# lednode2.net
KiCad netlist of a schematic drawn in EAGLE
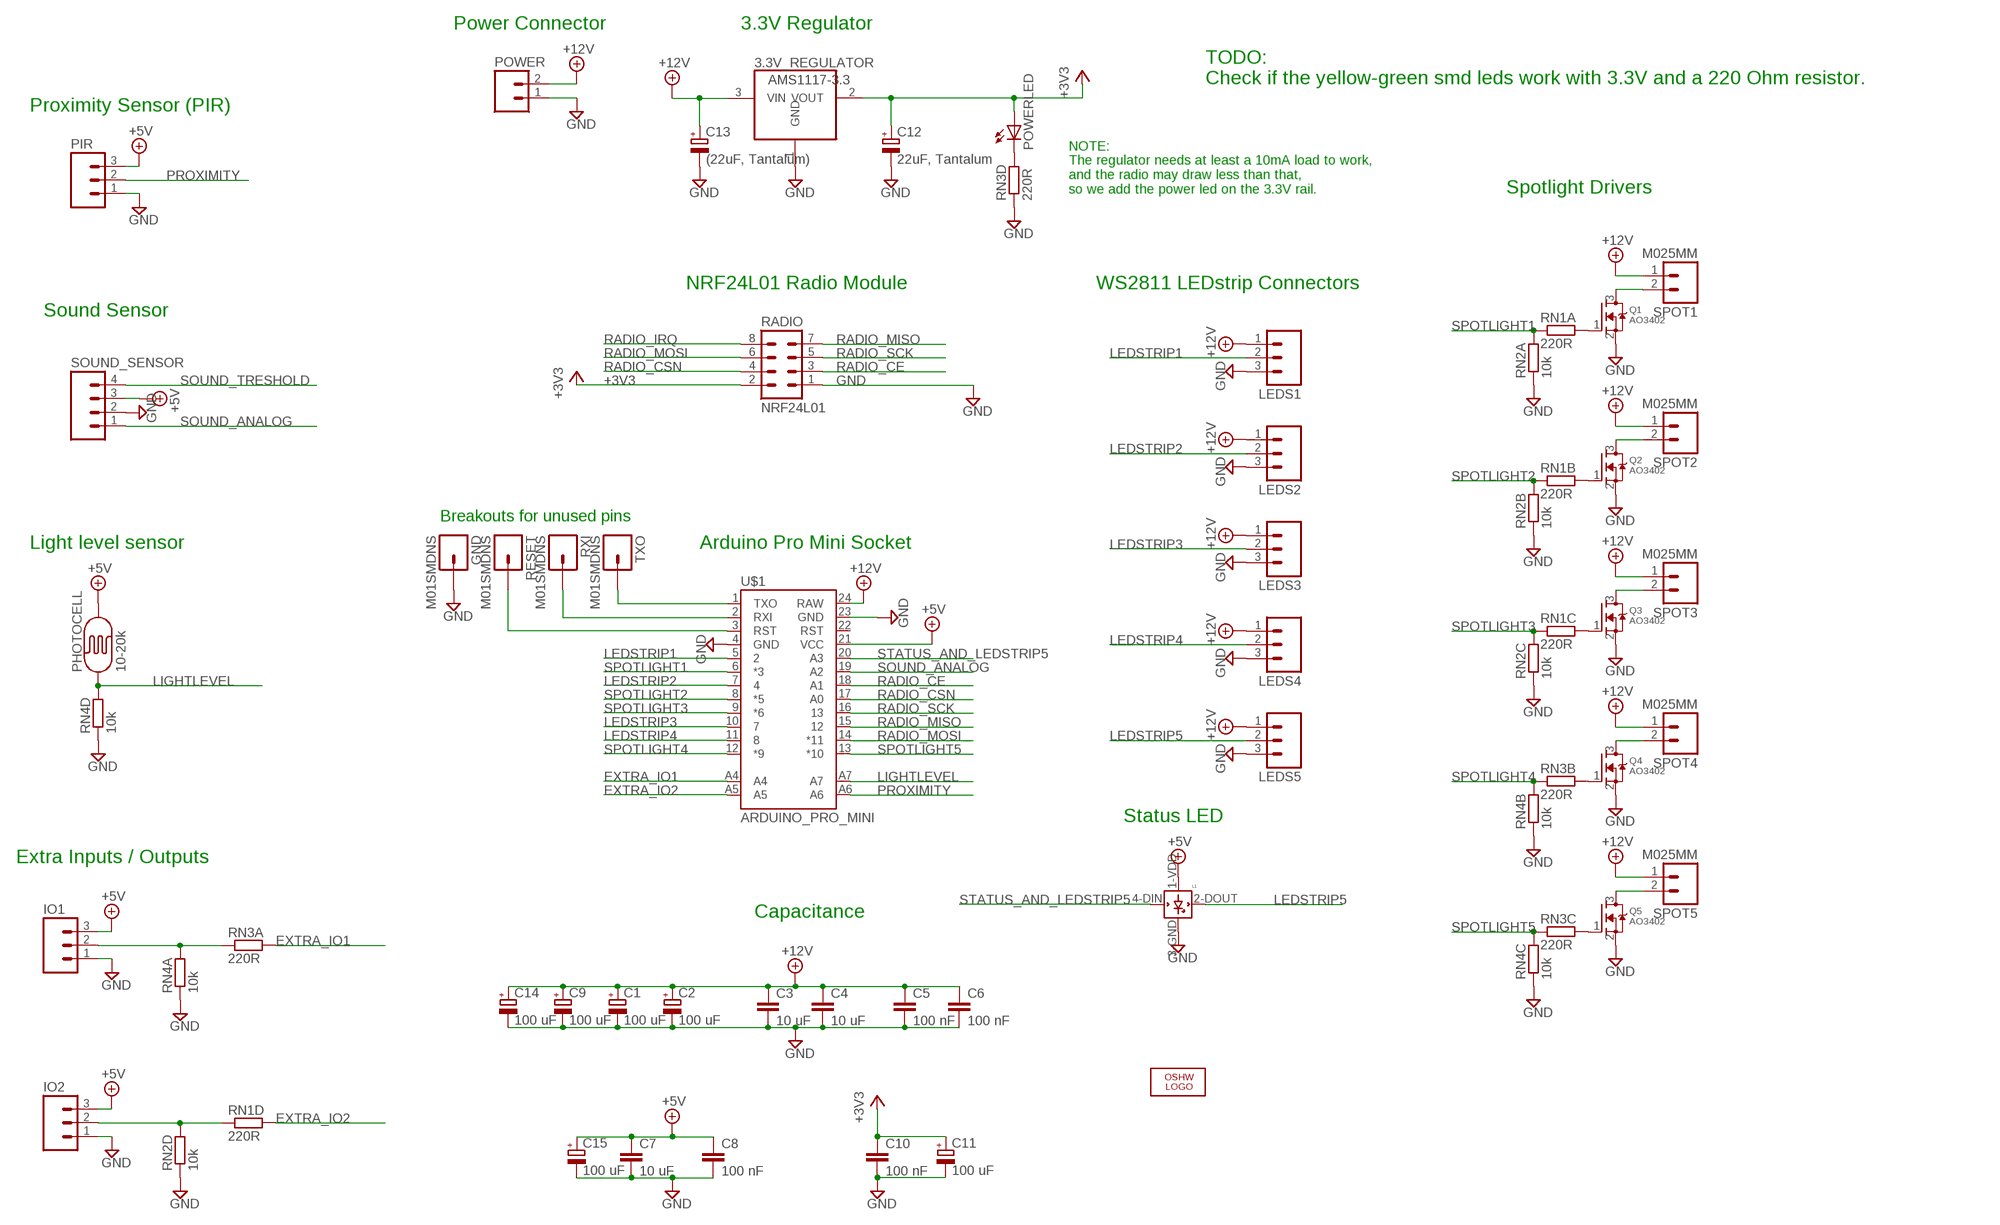
[diagram p0: schematic, sheet 1]

(export (version "E")
  (design (tool "Eeschema 10.0.6"))
  (components
    (comp (ref "3.3V_REGULATOR")
      (value "AMS1117-3.3")
      (footprint "eagle-import:SOT223")
      (fields (field (name "MPN") "REG1117"))
      (libsource (lib "eagle-import") (part "REG1117"))
    )
    (comp (ref "C1")
      (value "100 uF")
      (footprint "eagle-import:E2,5-6")
      (libsource (lib "eagle-import") (part "CPOL-EUE2.5-6"))
    )
    (comp (ref "C2")
      (value "100 uF")
      (footprint "eagle-import:E2,5-6")
      (libsource (lib "eagle-import") (part "CPOL-EUE2.5-6"))
    )
    (comp (ref "C3")
      (value "10 uF")
      (footprint "eagle-import:C1206")
      (libsource (lib "eagle-import") (part "C-EUC1206"))
    )
    (comp (ref "C4")
      (value "10 uF")
      (footprint "eagle-import:C1206")
      (libsource (lib "eagle-import") (part "C-EUC1206"))
    )
    (comp (ref "C5")
      (value "100 nF")
      (footprint "eagle-import:C0805")
      (libsource (lib "eagle-import") (part "C-EUC0805"))
    )
    (comp (ref "C6")
      (value "100 nF")
      (footprint "eagle-import:C0805")
      (libsource (lib "eagle-import") (part "C-EUC0805"))
    )
    (comp (ref "C7")
      (value "10 uF")
      (footprint "eagle-import:C1206")
      (libsource (lib "eagle-import") (part "C-EUC1206"))
    )
    (comp (ref "C8")
      (value "100 nF")
      (footprint "eagle-import:C0805")
      (libsource (lib "eagle-import") (part "C-EUC0805"))
    )
    (comp (ref "C9")
      (value "100 uF")
      (footprint "eagle-import:E2,5-6")
      (libsource (lib "eagle-import") (part "CPOL-EUE2.5-6"))
    )
    (comp (ref "C10")
      (value "100 nF")
      (footprint "eagle-import:C0805")
      (libsource (lib "eagle-import") (part "C-EUC0805"))
    )
    (comp (ref "C11")
      (value "100 uF")
      (footprint "eagle-import:E2,5-6")
      (libsource (lib "eagle-import") (part "CPOL-EUE2.5-6"))
    )
    (comp (ref "C12")
      (value "22uF, Tantalum")
      (footprint "eagle-import:SMC_A")
      (libsource (lib "eagle-import") (part "CPOL-EUSMCA"))
    )
    (comp (ref "C13")
      (value "(22uF, Tantalum)")
      (footprint "eagle-import:SMC_A")
      (libsource (lib "eagle-import") (part "CPOL-EUSMCA"))
    )
    (comp (ref "C14")
      (value "100 uF")
      (footprint "eagle-import:E2,5-6")
      (libsource (lib "eagle-import") (part "CPOL-EUE2.5-6"))
    )
    (comp (ref "C15")
      (value "100 uF")
      (footprint "eagle-import:E2,5-6")
      (libsource (lib "eagle-import") (part "CPOL-EUE2.5-6"))
    )
    (comp (ref "GND")
      (value "M01SMDNS")
      (footprint "eagle-import:1X01NS")
      (libsource (lib "eagle-import") (part "M01SMDNS"))
    )
    (comp (ref "IO1")
      (value "M03PTH")
      (footprint "eagle-import:1X03")
      (libsource (lib "eagle-import") (part "M03PTH"))
    )
    (comp (ref "IO2")
      (value "M03PTH")
      (footprint "eagle-import:1X03")
      (libsource (lib "eagle-import") (part "M03PTH"))
    )
    (comp (ref "L1")
      (value "WS2812B")
      (footprint "eagle-import:WS2812B")
      (libsource (lib "eagle-import") (part "WS2812B"))
    )
    (comp (ref "LEDS1")
      (value "M03LONGPADS")
      (footprint "eagle-import:1X03_LONGPADS")
      (libsource (lib "eagle-import") (part "M03LONGPADS"))
    )
    (comp (ref "LEDS2")
      (value "M03LONGPADS")
      (footprint "eagle-import:1X03_LONGPADS")
      (libsource (lib "eagle-import") (part "M03LONGPADS"))
    )
    (comp (ref "LEDS3")
      (value "M03LONGPADS")
      (footprint "eagle-import:1X03_LONGPADS")
      (libsource (lib "eagle-import") (part "M03LONGPADS"))
    )
    (comp (ref "LEDS4")
      (value "M03LONGPADS")
      (footprint "eagle-import:1X03_LONGPADS")
      (libsource (lib "eagle-import") (part "M03LONGPADS"))
    )
    (comp (ref "LEDS5")
      (value "M03LONGPADS")
      (footprint "eagle-import:1X03_LONGPADS")
      (libsource (lib "eagle-import") (part "M03LONGPADS"))
    )
    (comp (ref "LOGO3")
      (value "LOGO-OSHW-8MILX0100-NT")
      (footprint "eagle-import:OSHW_8X100_NOTEXT")
      (libsource (lib "eagle-import") (part "LOGO-OSHW-8MILX0100-NT"))
    )
    (comp (ref "PHOTOCELL")
      (value "10-20k")
      (footprint "eagle-import:PHOTOCELL")
      (libsource (lib "eagle-import") (part "PHOTOCELLPTH"))
    )
    (comp (ref "PIR")
      (value "M03PTH")
      (footprint "eagle-import:1X03")
      (libsource (lib "eagle-import") (part "M03PTH"))
    )
    (comp (ref "POWER")
      (value "M025MM")
      (footprint "eagle-import:SCREWTERMINAL-5MM-2")
      (libsource (lib "eagle-import") (part "M025MM"))
    )
    (comp (ref "POWERLED")
      (value "LEDSMT1206")
      (footprint "eagle-import:1206")
      (libsource (lib "eagle-import") (part "LEDSMT1206"))
    )
    (comp (ref "Q1")
      (value "AO3402")
      (footprint "eagle-import:SOT23-W")
      (libsource (lib "eagle-import") (part "MOSFET-NWAVE"))
    )
    (comp (ref "Q2")
      (value "AO3402")
      (footprint "eagle-import:SOT23-W")
      (libsource (lib "eagle-import") (part "MOSFET-NWAVE"))
    )
    (comp (ref "Q3")
      (value "AO3402")
      (footprint "eagle-import:SOT23-W")
      (libsource (lib "eagle-import") (part "MOSFET-NWAVE"))
    )
    (comp (ref "Q4")
      (value "AO3402")
      (footprint "eagle-import:SOT23-W")
      (libsource (lib "eagle-import") (part "MOSFET-NWAVE"))
    )
    (comp (ref "Q5")
      (value "AO3402")
      (footprint "eagle-import:SOT23-W")
      (libsource (lib "eagle-import") (part "MOSFET-NWAVE"))
    )
    (comp (ref "RADIO")
      (value "NRF24L01")
      (footprint "eagle-import:MA04-2")
      (libsource (lib "eagle-import") (part "MA04-2"))
    )
    (comp (ref "RESET")
      (value "M01SMDNS")
      (footprint "eagle-import:1X01NS")
      (libsource (lib "eagle-import") (part "M01SMDNS"))
    )
    (comp (ref "RN1")
      (value "220R")
      (footprint "eagle-import:RN8P-4R-CRA06S")
      (libsource (lib "eagle-import") (part "RESISTOR_ARRAY_4"))
    )
    (comp (ref "RN2")
      (value "10k")
      (footprint "eagle-import:RN8P-4R-CRA06S")
      (libsource (lib "eagle-import") (part "RESISTOR_ARRAY_4"))
    )
    (comp (ref "RN3")
      (value "220R")
      (footprint "eagle-import:RN8P-4R-CRA06S")
      (libsource (lib "eagle-import") (part "RESISTOR_ARRAY_4"))
    )
    (comp (ref "RN4")
      (value "10k")
      (footprint "eagle-import:RN8P-4R-CRA06S")
      (libsource (lib "eagle-import") (part "RESISTOR_ARRAY_4"))
    )
    (comp (ref "RXI")
      (value "M01SMDNS")
      (footprint "eagle-import:1X01NS")
      (libsource (lib "eagle-import") (part "M01SMDNS"))
    )
    (comp (ref "SOUND_SENSOR")
      (value "M041X04_NO_SILK")
      (footprint "eagle-import:1X04_NO_SILK")
      (libsource (lib "eagle-import") (part "M041X04_NO_SILK"))
    )
    (comp (ref "SPOT1")
      (value "M025MM")
      (footprint "eagle-import:SCREWTERMINAL-5MM-2")
      (libsource (lib "eagle-import") (part "SparkFun-Connectors_M025MM"))
    )
    (comp (ref "SPOT2")
      (value "M025MM")
      (footprint "eagle-import:SCREWTERMINAL-5MM-2")
      (libsource (lib "eagle-import") (part "SparkFun-Connectors_M025MM"))
    )
    (comp (ref "SPOT3")
      (value "M025MM")
      (footprint "eagle-import:SCREWTERMINAL-5MM-2")
      (libsource (lib "eagle-import") (part "SparkFun-Connectors_M025MM"))
    )
    (comp (ref "SPOT4")
      (value "M025MM")
      (footprint "eagle-import:SCREWTERMINAL-5MM-2")
      (libsource (lib "eagle-import") (part "SparkFun-Connectors_M025MM"))
    )
    (comp (ref "SPOT5")
      (value "M025MM")
      (footprint "eagle-import:SCREWTERMINAL-5MM-2")
      (libsource (lib "eagle-import") (part "SparkFun-Connectors_M025MM"))
    )
    (comp (ref "TXO")
      (value "M01SMDNS")
      (footprint "eagle-import:1X01NS")
      (libsource (lib "eagle-import") (part "M01SMDNS"))
    )
    (comp (ref "U$1")
      (value "ARDUINO_PRO_MINI")
      (footprint "eagle-import:ARDUINO_PRO_MINI")
      (libsource (lib "eagle-import") (part "ARDUINO_PRO_MINI"))
    )
  )
  (nets
    (net (code "1") (name "+3V3") (class "Default")
      (node (ref "3.3V_REGULATOR") (pin "2") (pinfunction "VOUT_2") (pintype "output"))
      (node (ref "C10") (pin "1") (pinfunction "1_1") (pintype "passive"))
      (node (ref "C11") (pin "+") (pinfunction "+_+") (pintype "passive"))
      (node (ref "C12") (pin "+") (pinfunction "+_+") (pintype "passive"))
      (node (ref "POWERLED") (pin "A") (pinfunction "A_A") (pintype "passive"))
      (node (ref "RADIO") (pin "2") (pinfunction "2_2") (pintype "passive"))
    )
    (net (code "2") (name "+5V") (class "Default")
      (node (ref "C15") (pin "+") (pinfunction "+_+") (pintype "passive"))
      (node (ref "C7") (pin "1") (pinfunction "1_1") (pintype "passive"))
      (node (ref "C8") (pin "1") (pinfunction "1_1") (pintype "passive"))
      (node (ref "IO1") (pin "3") (pinfunction "3_3") (pintype "passive"))
      (node (ref "IO2") (pin "3") (pinfunction "3_3") (pintype "passive"))
      (node (ref "L1") (pin "1-VDD") (pinfunction "VDD_1-VDD") (pintype "bidirectional"))
      (node (ref "PHOTOCELL") (pin "2") (pinfunction "P$2_2") (pintype "bidirectional"))
      (node (ref "PIR") (pin "3") (pinfunction "3_3") (pintype "passive"))
      (node (ref "SOUND_SENSOR") (pin "3") (pinfunction "3_3") (pintype "passive"))
      (node (ref "U$1") (pin "21") (pinfunction "VCC_21") (pintype "bidirectional"))
    )
    (net (code "3") (name "+12V") (class "Default")
      (node (ref "3.3V_REGULATOR") (pin "3") (pinfunction "VIN_3") (pintype "input"))
      (node (ref "C1") (pin "+") (pinfunction "+_+") (pintype "passive"))
      (node (ref "C13") (pin "+") (pinfunction "+_+") (pintype "passive"))
      (node (ref "C14") (pin "+") (pinfunction "+_+") (pintype "passive"))
      (node (ref "C2") (pin "+") (pinfunction "+_+") (pintype "passive"))
      (node (ref "C3") (pin "1") (pinfunction "1_1") (pintype "passive"))
      (node (ref "C4") (pin "1") (pinfunction "1_1") (pintype "passive"))
      (node (ref "C5") (pin "1") (pinfunction "1_1") (pintype "passive"))
      (node (ref "C6") (pin "1") (pinfunction "1_1") (pintype "passive"))
      (node (ref "C9") (pin "+") (pinfunction "+_+") (pintype "passive"))
      (node (ref "LEDS1") (pin "1") (pinfunction "1_1") (pintype "passive"))
      (node (ref "LEDS2") (pin "1") (pinfunction "1_1") (pintype "passive"))
      (node (ref "LEDS3") (pin "1") (pinfunction "1_1") (pintype "passive"))
      (node (ref "LEDS4") (pin "1") (pinfunction "1_1") (pintype "passive"))
      (node (ref "LEDS5") (pin "1") (pinfunction "1_1") (pintype "passive"))
      (node (ref "POWER") (pin "2") (pinfunction "2_2") (pintype "passive"))
      (node (ref "SPOT1") (pin "1") (pinfunction "1_1") (pintype "passive"))
      (node (ref "SPOT2") (pin "1") (pinfunction "1_1") (pintype "passive"))
      (node (ref "SPOT3") (pin "1") (pinfunction "1_1") (pintype "passive"))
      (node (ref "SPOT4") (pin "1") (pinfunction "1_1") (pintype "passive"))
      (node (ref "SPOT5") (pin "1") (pinfunction "1_1") (pintype "passive"))
      (node (ref "U$1") (pin "24") (pinfunction "RAW_24") (pintype "bidirectional"))
    )
    (net (code "4") (name "/EXTRA_IO1") (class "Default")
      (node (ref "RN3") (pin "8") (pinfunction "2_8") (pintype "passive"))
      (node (ref "U$1") (pin "A4") (pinfunction "A4_A4") (pintype "bidirectional"))
    )
    (net (code "5") (name "/EXTRA_IO2") (class "Default")
      (node (ref "RN1") (pin "5") (pinfunction "2_5") (pintype "passive"))
      (node (ref "U$1") (pin "A5") (pinfunction "A5_A5") (pintype "bidirectional"))
    )
    (net (code "6") (name "/LEDSTRIP1") (class "Default")
      (node (ref "LEDS1") (pin "2") (pinfunction "2_2") (pintype "passive"))
      (node (ref "U$1") (pin "5") (pinfunction "2_5") (pintype "bidirectional"))
    )
    (net (code "7") (name "/LEDSTRIP2") (class "Default")
      (node (ref "LEDS2") (pin "2") (pinfunction "2_2") (pintype "passive"))
      (node (ref "U$1") (pin "7") (pinfunction "4_7") (pintype "bidirectional"))
    )
    (net (code "8") (name "/LEDSTRIP3") (class "Default")
      (node (ref "LEDS3") (pin "2") (pinfunction "2_2") (pintype "passive"))
      (node (ref "U$1") (pin "10") (pinfunction "7_10") (pintype "bidirectional"))
    )
    (net (code "9") (name "/LEDSTRIP4") (class "Default")
      (node (ref "LEDS4") (pin "2") (pinfunction "2_2") (pintype "passive"))
      (node (ref "U$1") (pin "11") (pinfunction "8_11") (pintype "bidirectional"))
    )
    (net (code "10") (name "/LEDSTRIP5") (class "Default")
      (node (ref "L1") (pin "2-DOUT") (pinfunction "DOUT_2-DOUT") (pintype "output"))
      (node (ref "LEDS5") (pin "2") (pinfunction "2_2") (pintype "passive"))
    )
    (net (code "11") (name "/LIGHTLEVEL") (class "Default")
      (node (ref "PHOTOCELL") (pin "1") (pinfunction "P$1_1") (pintype "bidirectional"))
      (node (ref "RN4") (pin "5") (pinfunction "2_5") (pintype "passive"))
      (node (ref "U$1") (pin "A7") (pinfunction "A7_A7") (pintype "bidirectional"))
    )
    (net (code "12") (name "/PROXIMITY") (class "Default")
      (node (ref "PIR") (pin "2") (pinfunction "2_2") (pintype "passive"))
      (node (ref "U$1") (pin "A6") (pinfunction "A6_A6") (pintype "bidirectional"))
    )
    (net (code "13") (name "/RADIO_CE") (class "Default")
      (node (ref "RADIO") (pin "3") (pinfunction "3_3") (pintype "passive"))
      (node (ref "U$1") (pin "18") (pinfunction "A1_18") (pintype "bidirectional"))
    )
    (net (code "14") (name "/RADIO_CSN") (class "Default")
      (node (ref "RADIO") (pin "4") (pinfunction "4_4") (pintype "passive"))
      (node (ref "U$1") (pin "17") (pinfunction "A0_17") (pintype "bidirectional"))
    )
    (net (code "15") (name "/RADIO_IRQ") (class "Default")
      (node (ref "RADIO") (pin "8") (pinfunction "8_8") (pintype "passive"))
    )
    (net (code "16") (name "/RADIO_MISO") (class "Default")
      (node (ref "RADIO") (pin "7") (pinfunction "7_7") (pintype "passive"))
      (node (ref "U$1") (pin "15") (pinfunction "12_15") (pintype "bidirectional"))
    )
    (net (code "17") (name "/RADIO_MOSI") (class "Default")
      (node (ref "RADIO") (pin "6") (pinfunction "6_6") (pintype "passive"))
      (node (ref "U$1") (pin "14") (pinfunction "*11_14") (pintype "bidirectional"))
    )
    (net (code "18") (name "/RADIO_SCK") (class "Default")
      (node (ref "RADIO") (pin "5") (pinfunction "5_5") (pintype "passive"))
      (node (ref "U$1") (pin "16") (pinfunction "13_16") (pintype "bidirectional"))
    )
    (net (code "19") (name "/SOUND_ANALOG") (class "Default")
      (node (ref "SOUND_SENSOR") (pin "1") (pinfunction "1_1") (pintype "passive"))
      (node (ref "U$1") (pin "19") (pinfunction "A2_19") (pintype "bidirectional"))
    )
    (net (code "20") (name "/SOUND_TRESHOLD") (class "Default")
      (node (ref "SOUND_SENSOR") (pin "4") (pinfunction "4_4") (pintype "passive"))
    )
    (net (code "21") (name "/SPOTLIGHT1") (class "Default")
      (node (ref "RN1") (pin "1") (pinfunction "1_1") (pintype "passive"))
      (node (ref "RN2") (pin "8") (pinfunction "2_8") (pintype "passive"))
      (node (ref "U$1") (pin "6") (pinfunction "*3_6") (pintype "bidirectional"))
    )
    (net (code "22") (name "/SPOTLIGHT2") (class "Default")
      (node (ref "RN1") (pin "2") (pinfunction "1_2") (pintype "passive"))
      (node (ref "RN2") (pin "7") (pinfunction "2_7") (pintype "passive"))
      (node (ref "U$1") (pin "8") (pinfunction "*5_8") (pintype "bidirectional"))
    )
    (net (code "23") (name "/SPOTLIGHT3") (class "Default")
      (node (ref "RN1") (pin "3") (pinfunction "1_3") (pintype "passive"))
      (node (ref "RN2") (pin "6") (pinfunction "2_6") (pintype "passive"))
      (node (ref "U$1") (pin "9") (pinfunction "*6_9") (pintype "bidirectional"))
    )
    (net (code "24") (name "/SPOTLIGHT4") (class "Default")
      (node (ref "RN3") (pin "2") (pinfunction "1_2") (pintype "passive"))
      (node (ref "RN4") (pin "7") (pinfunction "2_7") (pintype "passive"))
      (node (ref "U$1") (pin "12") (pinfunction "*9_12") (pintype "bidirectional"))
    )
    (net (code "25") (name "/SPOTLIGHT5") (class "Default")
      (node (ref "RN3") (pin "3") (pinfunction "1_3") (pintype "passive"))
      (node (ref "RN4") (pin "6") (pinfunction "2_6") (pintype "passive"))
      (node (ref "U$1") (pin "13") (pinfunction "*10_13") (pintype "bidirectional"))
    )
    (net (code "26") (name "/STATUS_AND_LEDSTRIP5") (class "Default")
      (node (ref "L1") (pin "4-DIN") (pinfunction "DIN_4-DIN") (pintype "input"))
      (node (ref "U$1") (pin "20") (pinfunction "A3_20") (pintype "bidirectional"))
    )
    (net (code "27") (name "GND") (class "Default")
      (node (ref "3.3V_REGULATOR") (pin "1") (pinfunction "GND_1") (pintype "power_in"))
      (node (ref "C1") (pin "-") (pinfunction "-_-") (pintype "passive"))
      (node (ref "C10") (pin "2") (pinfunction "2_2") (pintype "passive"))
      (node (ref "C11") (pin "-") (pinfunction "-_-") (pintype "passive"))
      (node (ref "C12") (pin "-") (pinfunction "-_-") (pintype "passive"))
      (node (ref "C13") (pin "-") (pinfunction "-_-") (pintype "passive"))
      (node (ref "C14") (pin "-") (pinfunction "-_-") (pintype "passive"))
      (node (ref "C15") (pin "-") (pinfunction "-_-") (pintype "passive"))
      (node (ref "C2") (pin "-") (pinfunction "-_-") (pintype "passive"))
      (node (ref "C3") (pin "2") (pinfunction "2_2") (pintype "passive"))
      (node (ref "C4") (pin "2") (pinfunction "2_2") (pintype "passive"))
      (node (ref "C5") (pin "2") (pinfunction "2_2") (pintype "passive"))
      (node (ref "C6") (pin "2") (pinfunction "2_2") (pintype "passive"))
      (node (ref "C7") (pin "2") (pinfunction "2_2") (pintype "passive"))
      (node (ref "C8") (pin "2") (pinfunction "2_2") (pintype "passive"))
      (node (ref "C9") (pin "-") (pinfunction "-_-") (pintype "passive"))
      (node (ref "GND") (pin "1") (pinfunction "1_1") (pintype "passive"))
      (node (ref "IO1") (pin "1") (pinfunction "1_1") (pintype "passive"))
      (node (ref "IO2") (pin "1") (pinfunction "1_1") (pintype "passive"))
      (node (ref "L1") (pin "3-GND") (pinfunction "GND_3-GND") (pintype "bidirectional"))
      (node (ref "LEDS1") (pin "3") (pinfunction "3_3") (pintype "passive"))
      (node (ref "LEDS2") (pin "3") (pinfunction "3_3") (pintype "passive"))
      (node (ref "LEDS3") (pin "3") (pinfunction "3_3") (pintype "passive"))
      (node (ref "LEDS4") (pin "3") (pinfunction "3_3") (pintype "passive"))
      (node (ref "LEDS5") (pin "3") (pinfunction "3_3") (pintype "passive"))
      (node (ref "PIR") (pin "1") (pinfunction "1_1") (pintype "passive"))
      (node (ref "POWER") (pin "1") (pinfunction "1_1") (pintype "passive"))
      (node (ref "Q1") (pin "2") (pinfunction "S_2") (pintype "bidirectional"))
      (node (ref "Q2") (pin "2") (pinfunction "S_2") (pintype "bidirectional"))
      (node (ref "Q3") (pin "2") (pinfunction "S_2") (pintype "bidirectional"))
      (node (ref "Q4") (pin "2") (pinfunction "S_2") (pintype "bidirectional"))
      (node (ref "Q5") (pin "2") (pinfunction "S_2") (pintype "bidirectional"))
      (node (ref "RADIO") (pin "1") (pinfunction "1_1") (pintype "passive"))
      (node (ref "RN2") (pin "1") (pinfunction "1_1") (pintype "passive"))
      (node (ref "RN2") (pin "2") (pinfunction "1_2") (pintype "passive"))
      (node (ref "RN2") (pin "3") (pinfunction "1_3") (pintype "passive"))
      (node (ref "RN2") (pin "4") (pinfunction "1_4") (pintype "passive"))
      (node (ref "RN3") (pin "4") (pinfunction "1_4") (pintype "passive"))
      (node (ref "RN4") (pin "1") (pinfunction "1_1") (pintype "passive"))
      (node (ref "RN4") (pin "2") (pinfunction "1_2") (pintype "passive"))
      (node (ref "RN4") (pin "3") (pinfunction "1_3") (pintype "passive"))
      (node (ref "RN4") (pin "4") (pinfunction "1_4") (pintype "passive"))
      (node (ref "SOUND_SENSOR") (pin "2") (pinfunction "2_2") (pintype "passive"))
      (node (ref "U$1") (pin "23") (pinfunction "GND_23") (pintype "bidirectional"))
      (node (ref "U$1") (pin "4") (pinfunction "GND_4") (pintype "bidirectional"))
    )
    (net (code "28") (name "Net-(Q1-D)") (class "Default")
      (node (ref "Q1") (pin "3") (pinfunction "D_3") (pintype "bidirectional"))
      (node (ref "SPOT1") (pin "2") (pinfunction "2_2") (pintype "passive"))
    )
    (net (code "29") (name "Net-(Q1-G)") (class "Default")
      (node (ref "Q1") (pin "1") (pinfunction "G_1") (pintype "bidirectional"))
      (node (ref "RN1") (pin "8") (pinfunction "2_8") (pintype "passive"))
    )
    (net (code "30") (name "Net-(Q2-D)") (class "Default")
      (node (ref "Q2") (pin "3") (pinfunction "D_3") (pintype "bidirectional"))
      (node (ref "SPOT2") (pin "2") (pinfunction "2_2") (pintype "passive"))
    )
    (net (code "31") (name "Net-(Q2-G)") (class "Default")
      (node (ref "Q2") (pin "1") (pinfunction "G_1") (pintype "bidirectional"))
      (node (ref "RN1") (pin "7") (pinfunction "2_7") (pintype "passive"))
    )
    (net (code "32") (name "Net-(Q3-D)") (class "Default")
      (node (ref "Q3") (pin "3") (pinfunction "D_3") (pintype "bidirectional"))
      (node (ref "SPOT3") (pin "2") (pinfunction "2_2") (pintype "passive"))
    )
    (net (code "33") (name "Net-(Q3-G)") (class "Default")
      (node (ref "Q3") (pin "1") (pinfunction "G_1") (pintype "bidirectional"))
      (node (ref "RN1") (pin "6") (pinfunction "2_6") (pintype "passive"))
    )
    (net (code "34") (name "Net-(Q4-D)") (class "Default")
      (node (ref "Q4") (pin "3") (pinfunction "D_3") (pintype "bidirectional"))
      (node (ref "SPOT4") (pin "2") (pinfunction "2_2") (pintype "passive"))
    )
    (net (code "35") (name "Net-(Q4-G)") (class "Default")
      (node (ref "Q4") (pin "1") (pinfunction "G_1") (pintype "bidirectional"))
      (node (ref "RN3") (pin "7") (pinfunction "2_7") (pintype "passive"))
    )
    (net (code "36") (name "Net-(Q5-D)") (class "Default")
      (node (ref "Q5") (pin "3") (pinfunction "D_3") (pintype "bidirectional"))
      (node (ref "SPOT5") (pin "2") (pinfunction "2_2") (pintype "passive"))
    )
    (net (code "37") (name "Net-(Q5-G)") (class "Default")
      (node (ref "Q5") (pin "1") (pinfunction "G_1") (pintype "bidirectional"))
      (node (ref "RN3") (pin "6") (pinfunction "2_6") (pintype "passive"))
    )
    (net (code "38") (name "Net-(RESET-Pad1)") (class "Default")
      (node (ref "RESET") (pin "1") (pinfunction "1_1") (pintype "passive"))
      (node (ref "U$1") (pin "3") (pinfunction "RST_3") (pintype "bidirectional"))
    )
    (net (code "39") (name "Net-(RN1D-1)") (class "Default")
      (node (ref "IO2") (pin "2") (pinfunction "2_2") (pintype "passive"))
      (node (ref "RN1") (pin "4") (pinfunction "1_4") (pintype "passive"))
      (node (ref "RN2") (pin "5") (pinfunction "2_5") (pintype "passive"))
    )
    (net (code "40") (name "Net-(RN3D-2)") (class "Default")
      (node (ref "POWERLED") (pin "C") (pinfunction "C_C") (pintype "passive"))
      (node (ref "RN3") (pin "5") (pinfunction "2_5") (pintype "passive"))
    )
    (net (code "41") (name "Net-(RN4A-2)") (class "Default")
      (node (ref "IO1") (pin "2") (pinfunction "2_2") (pintype "passive"))
      (node (ref "RN3") (pin "1") (pinfunction "1_1") (pintype "passive"))
      (node (ref "RN4") (pin "8") (pinfunction "2_8") (pintype "passive"))
    )
    (net (code "42") (name "Net-(U$1-RXI)") (class "Default")
      (node (ref "RXI") (pin "1") (pinfunction "1_1") (pintype "passive"))
      (node (ref "U$1") (pin "2") (pinfunction "RXI_2") (pintype "bidirectional"))
    )
    (net (code "43") (name "Net-(U$1-TXO)") (class "Default")
      (node (ref "TXO") (pin "1") (pinfunction "1_1") (pintype "passive"))
      (node (ref "U$1") (pin "1") (pinfunction "TXO_1") (pintype "bidirectional"))
    )
    (net (code "44") (name "unconnected-(U$1-RST-Pad22)") (class "Default")
      (node (ref "U$1") (pin "22") (pinfunction "RST_22") (pintype "bidirectional"))
    )
  )
)
